# TM4C-A.net
KiCad netlist of a schematic drawn in Altium Designer
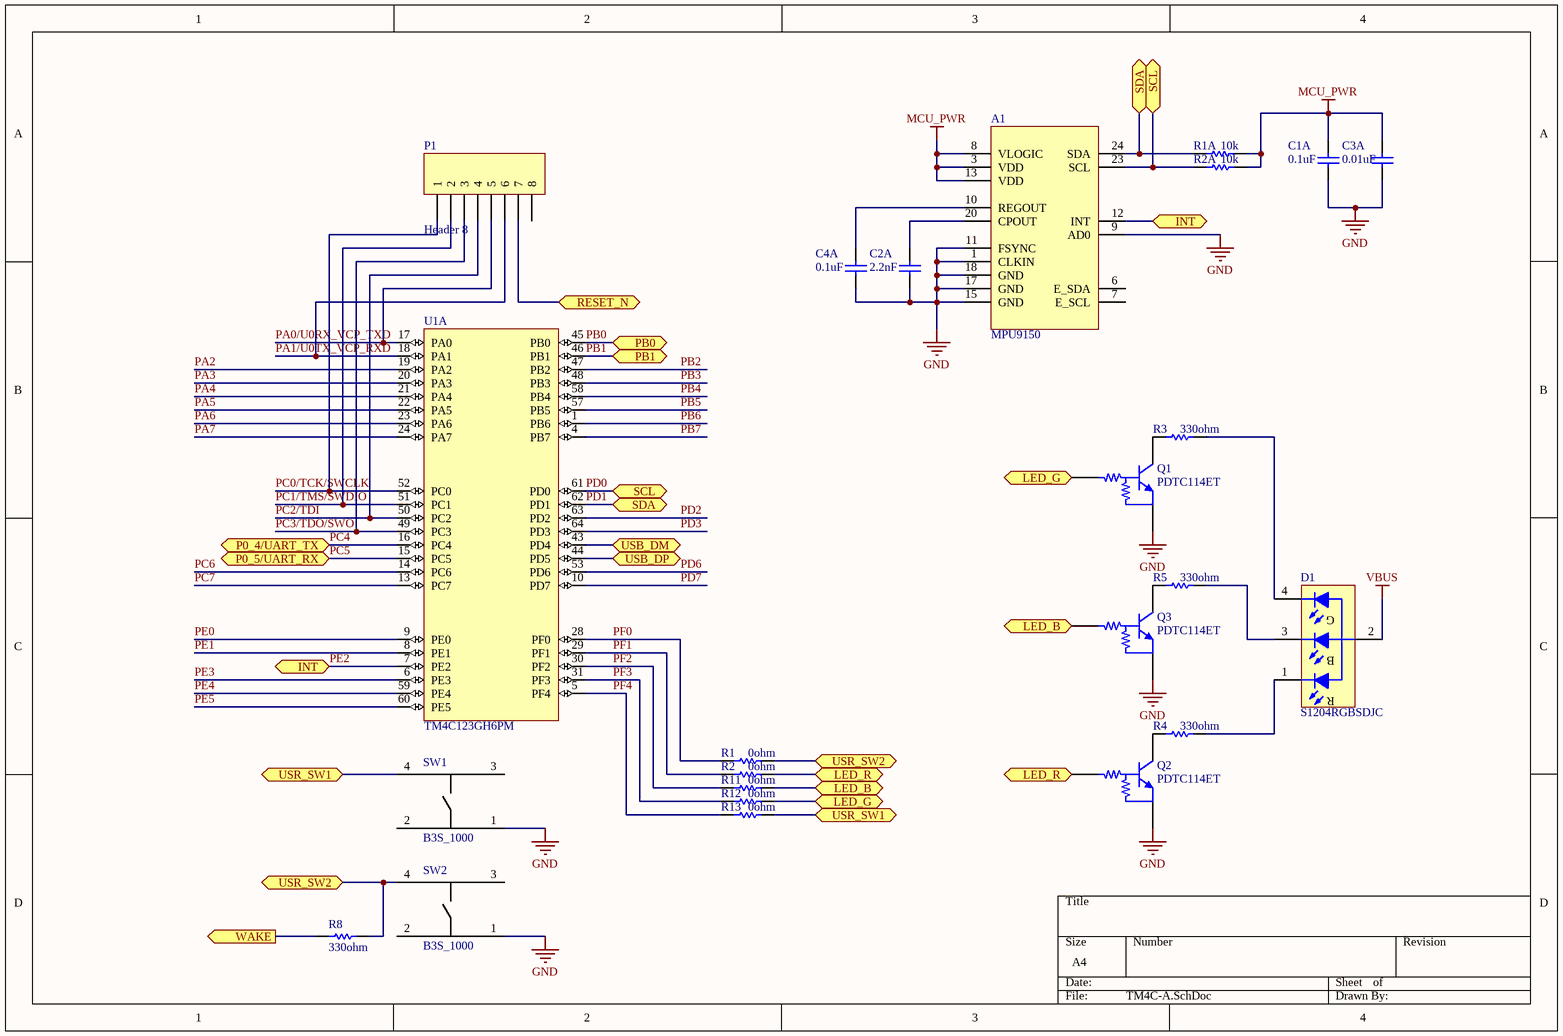
[diagram p0: TM4C-A.SchDoc]

(export (version "E")
  (design (tool "Eeschema 10.0.6"))
  (components
    (comp (ref "A1")
      (value "MPU9150")
      (footprint "MPU9150")
      (libsource (lib "TM4C_Launchpad") (part "MPU9150"))
    )
    (comp (ref "C1A")
      (value "0.1uF")
      (footprint "C0805")
      (description "Capacitor (Semiconductor SIM Model)")
      (fields (field (name "PUBLISHER") "Altium Limited"))
      (libsource (lib "Miscellaneous Devices") (part "Cap Semi"))
    )
    (comp (ref "C2A")
      (value "2.2nF")
      (footprint "C0805")
      (description "Capacitor (Semiconductor SIM Model)")
      (fields (field (name "PUBLISHER") "Altium Limited"))
      (libsource (lib "Miscellaneous Devices") (part "Cap Semi"))
    )
    (comp (ref "C3A")
      (value "0.01uF")
      (footprint "C0805")
      (description "Capacitor (Semiconductor SIM Model)")
      (fields (field (name "PUBLISHER") "Altium Limited"))
      (libsource (lib "Miscellaneous Devices") (part "Cap Semi"))
    )
    (comp (ref "C4A")
      (value "0.1uF")
      (footprint "C0805")
      (description "Capacitor (Semiconductor SIM Model)")
      (fields (field (name "PUBLISHER") "Altium Limited"))
      (libsource (lib "Miscellaneous Devices") (part "Cap Semi"))
    )
    (comp (ref "D1")
      (value "S1204RGBSDJC")
      (footprint "CLVBA-FKA")
      (description "Ultra-Bright RGB Tri-color LED Lamp, 4-Lead 1204-size SMD")
      (fields (field (name "PUBLISHER") "Altium Limited"))
      (libsource (lib "Sansen Optoelectronic LED") (part "S1204RGBSDJC"))
    )
    (comp (ref "P1")
      (value "Header 8")
      (footprint "HDR1X8")
      (description "Header, 8-Pin")
      (fields (field (name "PUBLISHER") "Altium Limited"))
      (libsource (lib "Miscellaneous Connectors") (part "Header 8"))
    )
    (comp (ref "Q1")
      (value "PDTC114ET")
      (footprint "SOT23_N")
      (description "NPN Resistor-equipped Transistor")
      (fields (field (name "PUBLISHER") "Altium Limited"))
      (libsource (lib "Philips Discrete BJT - Low Power") (part "PDTC114ET"))
    )
    (comp (ref "Q2")
      (value "PDTC114ET")
      (footprint "SOT23_N")
      (description "NPN Resistor-equipped Transistor")
      (fields (field (name "PUBLISHER") "Altium Limited"))
      (libsource (lib "Philips Discrete BJT - Low Power") (part "PDTC114ET"))
    )
    (comp (ref "Q3")
      (value "PDTC114ET")
      (footprint "SOT23_N")
      (description "NPN Resistor-equipped Transistor")
      (fields (field (name "PUBLISHER") "Altium Limited"))
      (libsource (lib "Philips Discrete BJT - Low Power") (part "PDTC114ET"))
    )
    (comp (ref "R1")
      (value "0ohm")
      (footprint "ERA-0805")
      (fields (field (name "PUBLISHER") "Altium Limited"))
      (libsource (lib "Panasonic Resistor") (part "ERAS"))
    )
    (comp (ref "R1A")
      (value "10k")
      (footprint "ERA-0805")
      (fields (field (name "PUBLISHER") "Altium Limited"))
      (libsource (lib "Panasonic Resistor") (part "ERAS"))
    )
    (comp (ref "R2")
      (value "0ohm")
      (footprint "ERA-0805")
      (fields (field (name "PUBLISHER") "Altium Limited"))
      (libsource (lib "Panasonic Resistor") (part "ERAS"))
    )
    (comp (ref "R2A")
      (value "10k")
      (footprint "ERA-0805")
      (fields (field (name "PUBLISHER") "Altium Limited"))
      (libsource (lib "Panasonic Resistor") (part "ERAS"))
    )
    (comp (ref "R3")
      (value "330ohm")
      (footprint "ERA-0805")
      (fields (field (name "PUBLISHER") "Altium Limited"))
      (libsource (lib "Panasonic Resistor") (part "ERAS"))
    )
    (comp (ref "R4")
      (value "330ohm")
      (footprint "ERA-0805")
      (fields (field (name "PUBLISHER") "Altium Limited"))
      (libsource (lib "Panasonic Resistor") (part "ERAS"))
    )
    (comp (ref "R5")
      (value "330ohm")
      (footprint "ERA-0805")
      (fields (field (name "PUBLISHER") "Altium Limited"))
      (libsource (lib "Panasonic Resistor") (part "ERAS"))
    )
    (comp (ref "R8")
      (value "330ohm")
      (footprint "ERA-0805")
      (fields (field (name "PUBLISHER") "Altium Limited"))
      (libsource (lib "Panasonic Resistor") (part "ERAS"))
    )
    (comp (ref "R11")
      (value "0ohm")
      (footprint "ERA-0805")
      (fields (field (name "PUBLISHER") "Altium Limited"))
      (libsource (lib "Panasonic Resistor") (part "ERAS"))
    )
    (comp (ref "R12")
      (value "0ohm")
      (footprint "ERA-0805")
      (fields (field (name "PUBLISHER") "Altium Limited"))
      (libsource (lib "Panasonic Resistor") (part "ERAS"))
    )
    (comp (ref "R13")
      (value "0ohm")
      (footprint "ERA-0805")
      (fields (field (name "PUBLISHER") "Altium Limited"))
      (libsource (lib "Panasonic Resistor") (part "ERAS"))
    )
    (comp (ref "SW1")
      (value "B3S_1000")
      (footprint "TM4C_Launchpad:B3S_1000")
      (libsource (lib "TM4C_Launchpad") (part "B3S_1000"))
    )
    (comp (ref "SW2")
      (value "B3S_1000")
      (footprint "TM4C_Launchpad:B3S_1000")
      (libsource (lib "TM4C_Launchpad") (part "B3S_1000"))
    )
    (comp (ref "U1")
      (value "TM4C123GH6PM")
      (footprint "LQFP64_L")
      (libsource (lib "TM4C_Launchpad") (part "TM4C123GH6PM"))
    )
  )
  (nets
    (net (code "1") (name "/LED_B") (class "Default")
      (node (ref "Q3") (pin "1") (pinfunction "B_1") (pintype "passive"))
      (node (ref "R11") (pin "2") (pinfunction "2_2") (pintype "passive"))
    )
    (net (code "2") (name "/LED_G") (class "Default")
      (node (ref "Q1") (pin "1") (pinfunction "B_1") (pintype "passive"))
      (node (ref "R12") (pin "2") (pinfunction "2_2") (pintype "passive"))
    )
    (net (code "3") (name "/LED_R") (class "Default")
      (node (ref "Q2") (pin "1") (pinfunction "B_1") (pintype "passive"))
      (node (ref "R2") (pin "2") (pinfunction "2_2") (pintype "passive"))
    )
    (net (code "4") (name "/PA0{slash}U0RX_VCP_TXD") (class "Default")
      (node (ref "P1") (pin "5") (pinfunction "5_5") (pintype "passive"))
      (node (ref "U1") (pin "17") (pinfunction "PA0_17") (pintype "bidirectional"))
    )
    (net (code "5") (name "/PA1{slash}U0TX_VCP_RXD") (class "Default")
      (node (ref "P1") (pin "6") (pinfunction "6_6") (pintype "passive"))
      (node (ref "U1") (pin "18") (pinfunction "PA1_18") (pintype "bidirectional"))
    )
    (net (code "6") (name "/PA2") (class "Default")
      (node (ref "U1") (pin "19") (pinfunction "PA2_19") (pintype "bidirectional"))
    )
    (net (code "7") (name "/PA3") (class "Default")
      (node (ref "U1") (pin "20") (pinfunction "PA3_20") (pintype "bidirectional"))
    )
    (net (code "8") (name "/PA4") (class "Default")
      (node (ref "U1") (pin "21") (pinfunction "PA4_21") (pintype "bidirectional"))
    )
    (net (code "9") (name "/PA5") (class "Default")
      (node (ref "U1") (pin "22") (pinfunction "PA5_22") (pintype "bidirectional"))
    )
    (net (code "10") (name "/PA6") (class "Default")
      (node (ref "U1") (pin "23") (pinfunction "PA6_23") (pintype "bidirectional"))
    )
    (net (code "11") (name "/PA7") (class "Default")
      (node (ref "U1") (pin "24") (pinfunction "PA7_24") (pintype "bidirectional"))
    )
    (net (code "12") (name "/PB0") (class "Default")
      (node (ref "U1") (pin "45") (pinfunction "PB0_45") (pintype "bidirectional"))
    )
    (net (code "13") (name "/PB1") (class "Default")
      (node (ref "U1") (pin "46") (pinfunction "PB1_46") (pintype "bidirectional"))
    )
    (net (code "14") (name "/PB2") (class "Default")
      (node (ref "U1") (pin "47") (pinfunction "PB2_47") (pintype "bidirectional"))
    )
    (net (code "15") (name "/PB3") (class "Default")
      (node (ref "U1") (pin "48") (pinfunction "PB3_48") (pintype "bidirectional"))
    )
    (net (code "16") (name "/PB4") (class "Default")
      (node (ref "U1") (pin "58") (pinfunction "PB4_58") (pintype "bidirectional"))
    )
    (net (code "17") (name "/PB5") (class "Default")
      (node (ref "U1") (pin "57") (pinfunction "PB5_57") (pintype "bidirectional"))
    )
    (net (code "18") (name "/PB6") (class "Default")
      (node (ref "U1") (pin "1") (pinfunction "PB6_1") (pintype "bidirectional"))
    )
    (net (code "19") (name "/PB7") (class "Default")
      (node (ref "U1") (pin "4") (pinfunction "PB7_4") (pintype "bidirectional"))
    )
    (net (code "20") (name "/PC0{slash}TCK{slash}SWCLK") (class "Default")
      (node (ref "P1") (pin "1") (pinfunction "1_1") (pintype "passive"))
      (node (ref "U1") (pin "52") (pinfunction "PC0_52") (pintype "bidirectional"))
    )
    (net (code "21") (name "/PC1{slash}TMS{slash}SWDIO") (class "Default")
      (node (ref "P1") (pin "2") (pinfunction "2_2") (pintype "passive"))
      (node (ref "U1") (pin "51") (pinfunction "PC1_51") (pintype "bidirectional"))
    )
    (net (code "22") (name "/PC2{slash}TDI") (class "Default")
      (node (ref "P1") (pin "4") (pinfunction "4_4") (pintype "passive"))
      (node (ref "U1") (pin "50") (pinfunction "PC2_50") (pintype "bidirectional"))
    )
    (net (code "23") (name "/PC3{slash}TDO{slash}SWO") (class "Default")
      (node (ref "P1") (pin "3") (pinfunction "3_3") (pintype "passive"))
      (node (ref "U1") (pin "49") (pinfunction "PC3_49") (pintype "bidirectional"))
    )
    (net (code "24") (name "/PC4") (class "Default")
      (node (ref "U1") (pin "16") (pinfunction "PC4_16") (pintype "bidirectional"))
    )
    (net (code "25") (name "/PC5") (class "Default")
      (node (ref "U1") (pin "15") (pinfunction "PC5_15") (pintype "bidirectional"))
    )
    (net (code "26") (name "/PC6") (class "Default")
      (node (ref "U1") (pin "14") (pinfunction "PC6_14") (pintype "bidirectional"))
    )
    (net (code "27") (name "/PC7") (class "Default")
      (node (ref "U1") (pin "13") (pinfunction "PC7_13") (pintype "bidirectional"))
    )
    (net (code "28") (name "/PD0") (class "Default")
      (node (ref "A1") (pin "23") (pinfunction "SCL_23") (pintype "passive"))
      (node (ref "R2A") (pin "2") (pinfunction "2_2") (pintype "passive"))
      (node (ref "U1") (pin "61") (pinfunction "PD0_61") (pintype "bidirectional"))
    )
    (net (code "29") (name "/PD1") (class "Default")
      (node (ref "A1") (pin "24") (pinfunction "SDA_24") (pintype "passive"))
      (node (ref "R1A") (pin "2") (pinfunction "2_2") (pintype "passive"))
      (node (ref "U1") (pin "62") (pinfunction "PD1_62") (pintype "bidirectional"))
    )
    (net (code "30") (name "/PD2") (class "Default")
      (node (ref "U1") (pin "63") (pinfunction "PD2_63") (pintype "bidirectional"))
    )
    (net (code "31") (name "/PD3") (class "Default")
      (node (ref "U1") (pin "64") (pinfunction "PD3_64") (pintype "bidirectional"))
    )
    (net (code "32") (name "/PD6") (class "Default")
      (node (ref "U1") (pin "53") (pinfunction "PD6_53") (pintype "bidirectional"))
    )
    (net (code "33") (name "/PD7") (class "Default")
      (node (ref "U1") (pin "10") (pinfunction "PD7_10") (pintype "bidirectional"))
    )
    (net (code "34") (name "/PE0") (class "Default")
      (node (ref "U1") (pin "9") (pinfunction "PE0_9") (pintype "bidirectional"))
    )
    (net (code "35") (name "/PE1") (class "Default")
      (node (ref "U1") (pin "8") (pinfunction "PE1_8") (pintype "bidirectional"))
    )
    (net (code "36") (name "/PE2") (class "Default")
      (node (ref "A1") (pin "12") (pinfunction "INT_12") (pintype "passive"))
      (node (ref "U1") (pin "7") (pinfunction "PE2_7") (pintype "bidirectional"))
    )
    (net (code "37") (name "/PE3") (class "Default")
      (node (ref "U1") (pin "6") (pinfunction "PE3_6") (pintype "bidirectional"))
    )
    (net (code "38") (name "/PE4") (class "Default")
      (node (ref "U1") (pin "59") (pinfunction "PE4_59") (pintype "bidirectional"))
    )
    (net (code "39") (name "/PE5") (class "Default")
      (node (ref "U1") (pin "60") (pinfunction "PE5_60") (pintype "bidirectional"))
    )
    (net (code "40") (name "/PF0") (class "Default")
      (node (ref "R1") (pin "1") (pinfunction "1_1") (pintype "passive"))
      (node (ref "U1") (pin "28") (pinfunction "PF0_28") (pintype "bidirectional"))
    )
    (net (code "41") (name "/PF1") (class "Default")
      (node (ref "R2") (pin "1") (pinfunction "1_1") (pintype "passive"))
      (node (ref "U1") (pin "29") (pinfunction "PF1_29") (pintype "bidirectional"))
    )
    (net (code "42") (name "/PF2") (class "Default")
      (node (ref "R11") (pin "1") (pinfunction "1_1") (pintype "passive"))
      (node (ref "U1") (pin "30") (pinfunction "PF2_30") (pintype "bidirectional"))
    )
    (net (code "43") (name "/PF3") (class "Default")
      (node (ref "R12") (pin "1") (pinfunction "1_1") (pintype "passive"))
      (node (ref "U1") (pin "31") (pinfunction "PF3_31") (pintype "bidirectional"))
    )
    (net (code "44") (name "/PF4") (class "Default")
      (node (ref "R13") (pin "1") (pinfunction "1_1") (pintype "passive"))
      (node (ref "U1") (pin "5") (pinfunction "PF4_5") (pintype "bidirectional"))
    )
    (net (code "45") (name "/RESET_N") (class "Default")
      (node (ref "P1") (pin "7") (pinfunction "7_7") (pintype "passive"))
    )
    (net (code "46") (name "/USB_DM") (class "Default")
      (node (ref "U1") (pin "43") (pinfunction "PD4_43") (pintype "bidirectional"))
    )
    (net (code "47") (name "/USB_DP") (class "Default")
      (node (ref "U1") (pin "44") (pinfunction "PD5_44") (pintype "bidirectional"))
    )
    (net (code "48") (name "/USR_SW1") (class "Default")
      (node (ref "R13") (pin "2") (pinfunction "2_2") (pintype "passive"))
      (node (ref "SW1") (pin "4") (pinfunction "4_4") (pintype "passive"))
    )
    (net (code "49") (name "/USR_SW2") (class "Default")
      (node (ref "R1") (pin "2") (pinfunction "2_2") (pintype "passive"))
      (node (ref "R8") (pin "2") (pinfunction "2_2") (pintype "passive"))
      (node (ref "SW2") (pin "4") (pinfunction "4_4") (pintype "passive"))
    )
    (net (code "50") (name "/WAKE") (class "Default")
      (node (ref "R8") (pin "1") (pinfunction "1_1") (pintype "passive"))
    )
    (net (code "51") (name "GND") (class "Default")
      (node (ref "A1") (pin "1") (pinfunction "CLKIN_1") (pintype "passive"))
      (node (ref "A1") (pin "11") (pinfunction "FSYNC_11") (pintype "passive"))
      (node (ref "A1") (pin "15") (pinfunction "GND_15") (pintype "passive"))
      (node (ref "A1") (pin "17") (pinfunction "GND_17") (pintype "passive"))
      (node (ref "A1") (pin "18") (pinfunction "GND_18") (pintype "passive"))
      (node (ref "A1") (pin "9") (pinfunction "AD0_9") (pintype "passive"))
      (node (ref "C1A") (pin "1") (pinfunction "1_1") (pintype "passive"))
      (node (ref "C2A") (pin "1") (pinfunction "1_1") (pintype "passive"))
      (node (ref "C3A") (pin "1") (pinfunction "1_1") (pintype "passive"))
      (node (ref "C4A") (pin "1") (pinfunction "1_1") (pintype "passive"))
      (node (ref "Q1") (pin "2") (pinfunction "E_2") (pintype "passive"))
      (node (ref "Q2") (pin "2") (pinfunction "E_2") (pintype "passive"))
      (node (ref "Q3") (pin "2") (pinfunction "E_2") (pintype "passive"))
      (node (ref "SW1") (pin "1") (pinfunction "1_1") (pintype "passive"))
      (node (ref "SW2") (pin "1") (pinfunction "1_1") (pintype "passive"))
    )
    (net (code "52") (name "MCU_PWR") (class "Default")
      (node (ref "A1") (pin "13") (pinfunction "VDD_13") (pintype "passive"))
      (node (ref "A1") (pin "3") (pinfunction "VDD_3") (pintype "passive"))
      (node (ref "A1") (pin "8") (pinfunction "VLOGIC_8") (pintype "passive"))
      (node (ref "C1A") (pin "2") (pinfunction "2_2") (pintype "passive"))
      (node (ref "C3A") (pin "2") (pinfunction "2_2") (pintype "passive"))
      (node (ref "R1A") (pin "1") (pinfunction "1_1") (pintype "passive"))
      (node (ref "R2A") (pin "1") (pinfunction "1_1") (pintype "passive"))
    )
    (net (code "53") (name "Net-(A1-CPOUT)") (class "Default")
      (node (ref "A1") (pin "20") (pinfunction "CPOUT_20") (pintype "passive"))
      (node (ref "C2A") (pin "2") (pinfunction "2_2") (pintype "passive"))
    )
    (net (code "54") (name "Net-(A1-REGOUT)") (class "Default")
      (node (ref "A1") (pin "10") (pinfunction "REGOUT_10") (pintype "passive"))
      (node (ref "C4A") (pin "2") (pinfunction "2_2") (pintype "passive"))
    )
    (net (code "55") (name "Net-(D1-B)") (class "Default")
      (node (ref "D1") (pin "3") (pinfunction "B_3") (pintype "passive"))
      (node (ref "R5") (pin "1") (pinfunction "1_1") (pintype "passive"))
    )
    (net (code "56") (name "Net-(D1-G)") (class "Default")
      (node (ref "D1") (pin "4") (pinfunction "G_4") (pintype "passive"))
      (node (ref "R3") (pin "1") (pinfunction "1_1") (pintype "passive"))
    )
    (net (code "57") (name "Net-(D1-R)") (class "Default")
      (node (ref "D1") (pin "1") (pinfunction "R_1") (pintype "passive"))
      (node (ref "R4") (pin "1") (pinfunction "1_1") (pintype "passive"))
    )
    (net (code "58") (name "Net-(Q1-C)") (class "Default")
      (node (ref "Q1") (pin "3") (pinfunction "C_3") (pintype "passive"))
      (node (ref "R3") (pin "2") (pinfunction "2_2") (pintype "passive"))
    )
    (net (code "59") (name "Net-(Q2-C)") (class "Default")
      (node (ref "Q2") (pin "3") (pinfunction "C_3") (pintype "passive"))
      (node (ref "R4") (pin "2") (pinfunction "2_2") (pintype "passive"))
    )
    (net (code "60") (name "Net-(Q3-C)") (class "Default")
      (node (ref "Q3") (pin "3") (pinfunction "C_3") (pintype "passive"))
      (node (ref "R5") (pin "2") (pinfunction "2_2") (pintype "passive"))
    )
    (net (code "61") (name "VBUS") (class "Default")
      (node (ref "D1") (pin "2") (pinfunction "A2_2") (pintype "passive"))
    )
    (net (code "62") (name "unconnected-(A1-E_SCL-Pad7)") (class "Default")
      (node (ref "A1") (pin "7") (pinfunction "E_SCL_7") (pintype "passive"))
    )
    (net (code "63") (name "unconnected-(A1-E_SDA-Pad6)") (class "Default")
      (node (ref "A1") (pin "6") (pinfunction "E_SDA_6") (pintype "passive"))
    )
    (net (code "64") (name "unconnected-(P1-Pad8)") (class "Default")
      (node (ref "P1") (pin "8") (pinfunction "8_8") (pintype "passive"))
    )
    (net (code "65") (name "unconnected-(SW1-Pad2)") (class "Default")
      (node (ref "SW1") (pin "2") (pinfunction "2_2") (pintype "passive"))
    )
    (net (code "66") (name "unconnected-(SW1-Pad3)") (class "Default")
      (node (ref "SW1") (pin "3") (pinfunction "3_3") (pintype "passive"))
    )
    (net (code "67") (name "unconnected-(SW2-Pad2)") (class "Default")
      (node (ref "SW2") (pin "2") (pinfunction "2_2") (pintype "passive"))
    )
    (net (code "68") (name "unconnected-(SW2-Pad3)") (class "Default")
      (node (ref "SW2") (pin "3") (pinfunction "3_3") (pintype "passive"))
    )
  )
)
